# HDN_Control_Data.net
KiCad netlist of a schematic drawn in Altium Designer
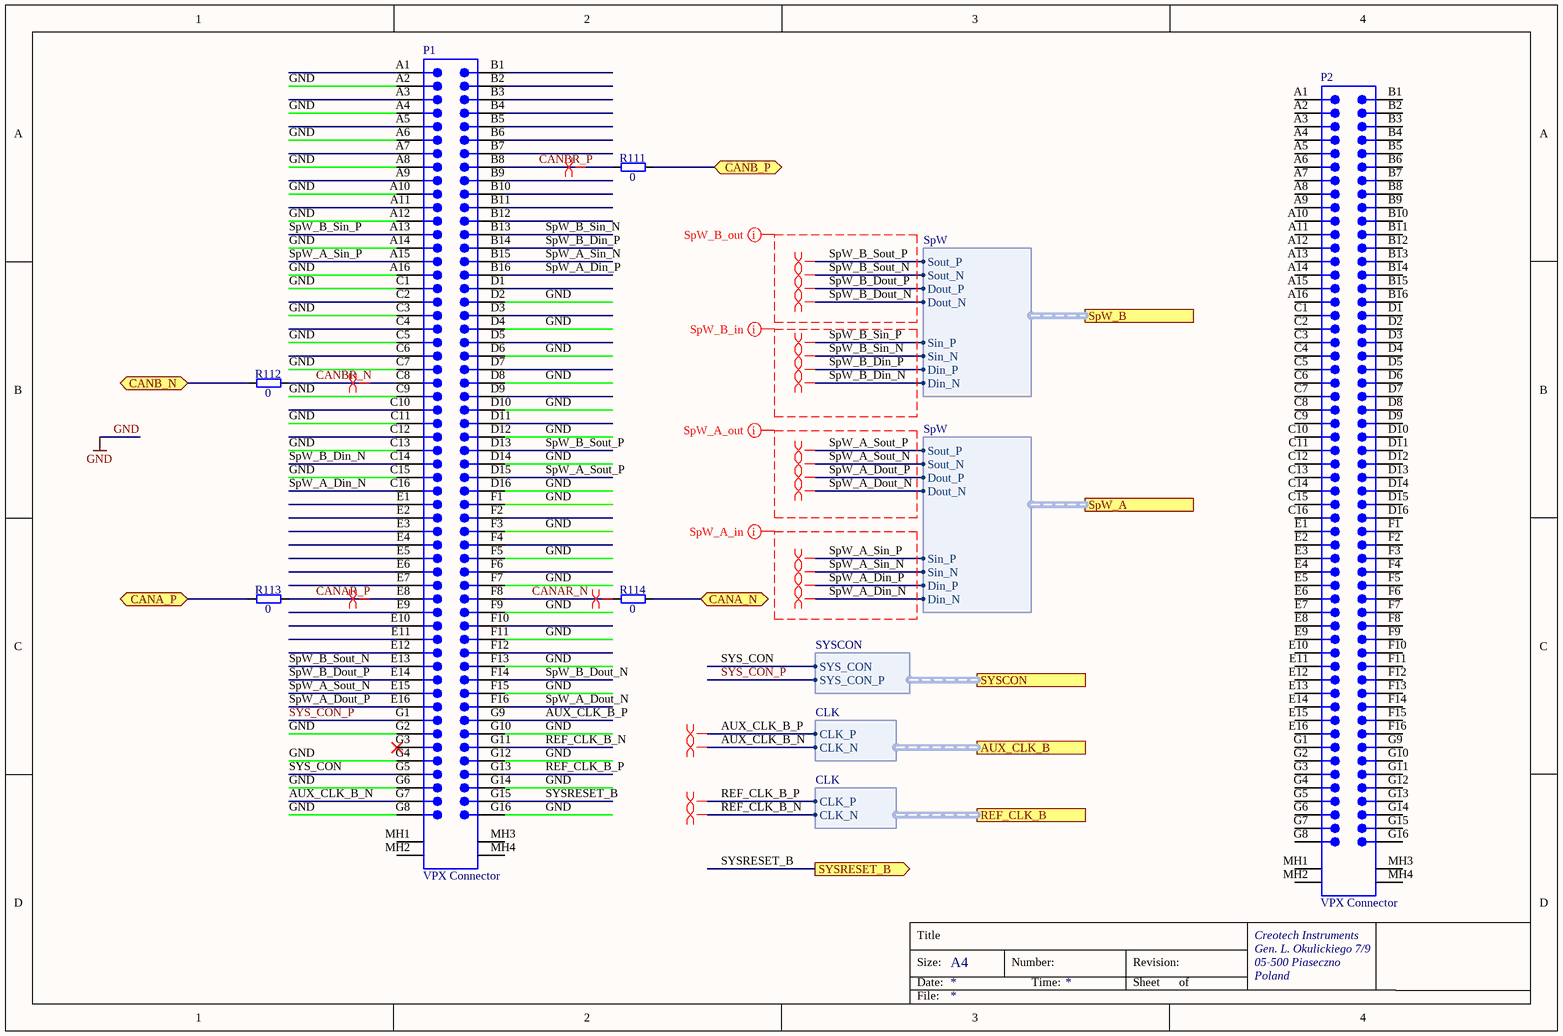
[diagram p0: HDN_Control_Data.SchDoc]

(export (version "E")
  (design (tool "Eeschema 10.0.6"))
  (components
    (comp (ref "P1")
      (value "VPX Connector")
      (footprint "BTB1-8-4H112M")
      (description "Board-to-Board Connector, Right Angle, 7-Row, Pitch 1.8mm, 112-Position")
      (fields (field (name "MANUFACTURER") "TE") (field (name "MANUFACTURER PART NUMBER") "1410187-3"))
      (libsource (lib "LIBRARY_SCH") (part "CON_VPX_1410187-3"))
    )
    (comp (ref "P2")
      (value "VPX Connector")
      (footprint "BTB1-8-4H112M")
      (description "Board-to-Board Connector, Right Angle, 7-Row, Pitch 1.8mm, 112-Position")
      (fields (field (name "MANUFACTURER") "TE") (field (name "MANUFACTURER PART NUMBER") "1410187-3"))
      (libsource (lib "LIBRARY_SCH") (part "CON_VPX_1410187-3"))
    )
    (comp (ref "R111")
      (value "0")
      (footprint "RESC1608X55N")
      (description "Resistor")
      (fields
        (field (name "PART NUMBER") "R0603_0R_JUMPER")
        (field (name "MANUFACTURER") "GENERIC")
        (field (name "AUTHOR") "CERN DEM JLC")
      )
      (libsource (lib "Resistors") (part "Resistor"))
    )
    (comp (ref "R112")
      (value "0")
      (footprint "RESC1608X55N")
      (description "Resistor")
      (fields
        (field (name "PART NUMBER") "R0603_0R_JUMPER")
        (field (name "MANUFACTURER") "GENERIC")
        (field (name "AUTHOR") "CERN DEM JLC")
      )
      (libsource (lib "Resistors") (part "Resistor"))
    )
    (comp (ref "R113")
      (value "0")
      (footprint "RESC1608X55N")
      (description "Resistor")
      (fields
        (field (name "PART NUMBER") "R0603_0R_JUMPER")
        (field (name "MANUFACTURER") "GENERIC")
        (field (name "AUTHOR") "CERN DEM JLC")
      )
      (libsource (lib "Resistors") (part "Resistor"))
    )
    (comp (ref "R114")
      (value "0")
      (footprint "RESC1608X55N")
      (description "Resistor")
      (fields
        (field (name "PART NUMBER") "R0603_0R_JUMPER")
        (field (name "MANUFACTURER") "GENERIC")
        (field (name "AUTHOR") "CERN DEM JLC")
      )
      (libsource (lib "Resistors") (part "Resistor"))
    )
  )
  (nets
    (net (code "4") (name "/AUX_CLK_B_N") (class "Default")
      (node (ref "P1") (pin "G7") (pinfunction "G7_G7") (pintype "passive"))
    )
    (net (code "5") (name "/AUX_CLK_B_P") (class "Default")
      (node (ref "P1") (pin "G9") (pinfunction "G9_G9") (pintype "passive"))
    )
    (net (code "6") (name "/CANAR_N") (class "Default")
      (node (ref "P1") (pin "F8") (pinfunction "F8_F8") (pintype "passive"))
      (node (ref "R114") (pin "1") (pinfunction "1_1") (pintype "passive"))
    )
    (net (code "7") (name "/CANAR_P") (class "Default")
      (node (ref "P1") (pin "E8") (pinfunction "E8_E8") (pintype "passive"))
      (node (ref "R113") (pin "2") (pinfunction "2_2") (pintype "passive"))
    )
    (net (code "8") (name "/CANA_N") (class "Default")
      (node (ref "R114") (pin "2") (pinfunction "2_2") (pintype "passive"))
    )
    (net (code "9") (name "/CANA_P") (class "Default")
      (node (ref "R113") (pin "1") (pinfunction "1_1") (pintype "passive"))
    )
    (net (code "10") (name "/CANBR_N") (class "Default")
      (node (ref "P1") (pin "C8") (pinfunction "C8_C8") (pintype "passive"))
      (node (ref "R112") (pin "2") (pinfunction "2_2") (pintype "passive"))
    )
    (net (code "11") (name "/CANBR_P") (class "Default")
      (node (ref "P1") (pin "B8") (pinfunction "B8_B8") (pintype "passive"))
      (node (ref "R111") (pin "1") (pinfunction "1_1") (pintype "passive"))
    )
    (net (code "12") (name "/CANB_N") (class "Default")
      (node (ref "R112") (pin "1") (pinfunction "1_1") (pintype "passive"))
    )
    (net (code "13") (name "/CANB_P") (class "Default")
      (node (ref "R111") (pin "2") (pinfunction "2_2") (pintype "passive"))
    )
    (net (code "14") (name "/REF_CLK_B_N") (class "Default")
      (node (ref "P1") (pin "G11") (pinfunction "G11_G11") (pintype "passive"))
    )
    (net (code "15") (name "/REF_CLK_B_P") (class "Default")
      (node (ref "P1") (pin "G13") (pinfunction "G13_G13") (pintype "passive"))
    )
    (net (code "16") (name "/SYSRESET_B") (class "Default")
      (node (ref "P1") (pin "G15") (pinfunction "G15_G15") (pintype "passive"))
    )
    (net (code "17") (name "/SYS_CON") (class "Default")
      (node (ref "P1") (pin "G5") (pinfunction "G5_G5") (pintype "passive"))
    )
    (net (code "18") (name "/SYS_CON_P") (class "Default")
      (node (ref "P1") (pin "G1") (pinfunction "G1_G1") (pintype "passive"))
    )
    (net (code "19") (name "/SpW_A_Din_N") (class "Default")
      (node (ref "P1") (pin "C16") (pinfunction "C16_C16") (pintype "passive"))
    )
    (net (code "20") (name "/SpW_A_Din_P") (class "Default")
      (node (ref "P1") (pin "B16") (pinfunction "B16_B16") (pintype "passive"))
    )
    (net (code "21") (name "/SpW_A_Dout_N") (class "Default")
      (node (ref "P1") (pin "F16") (pinfunction "F16_F16") (pintype "passive"))
    )
    (net (code "22") (name "/SpW_A_Dout_P") (class "Default")
      (node (ref "P1") (pin "E16") (pinfunction "E16_E16") (pintype "passive"))
    )
    (net (code "23") (name "/SpW_A_Sin_N") (class "Default")
      (node (ref "P1") (pin "B15") (pinfunction "B15_B15") (pintype "passive"))
    )
    (net (code "24") (name "/SpW_A_Sin_P") (class "Default")
      (node (ref "P1") (pin "A15") (pinfunction "A15_A15") (pintype "passive"))
    )
    (net (code "25") (name "/SpW_A_Sout_N") (class "Default")
      (node (ref "P1") (pin "E15") (pinfunction "E15_E15") (pintype "passive"))
    )
    (net (code "26") (name "/SpW_A_Sout_P") (class "Default")
      (node (ref "P1") (pin "D15") (pinfunction "D15_D15") (pintype "passive"))
    )
    (net (code "27") (name "/SpW_B_Din_N") (class "Default")
      (node (ref "P1") (pin "C14") (pinfunction "C14_C14") (pintype "passive"))
    )
    (net (code "28") (name "/SpW_B_Din_P") (class "Default")
      (node (ref "P1") (pin "B14") (pinfunction "B14_B14") (pintype "passive"))
    )
    (net (code "29") (name "/SpW_B_Dout_N") (class "Default")
      (node (ref "P1") (pin "F14") (pinfunction "F14_F14") (pintype "passive"))
    )
    (net (code "30") (name "/SpW_B_Dout_P") (class "Default")
      (node (ref "P1") (pin "E14") (pinfunction "E14_E14") (pintype "passive"))
    )
    (net (code "31") (name "/SpW_B_Sin_N") (class "Default")
      (node (ref "P1") (pin "B13") (pinfunction "B13_B13") (pintype "passive"))
    )
    (net (code "32") (name "/SpW_B_Sin_P") (class "Default")
      (node (ref "P1") (pin "A13") (pinfunction "A13_A13") (pintype "passive"))
    )
    (net (code "33") (name "/SpW_B_Sout_N") (class "Default")
      (node (ref "P1") (pin "E13") (pinfunction "E13_E13") (pintype "passive"))
    )
    (net (code "34") (name "/SpW_B_Sout_P") (class "Default")
      (node (ref "P1") (pin "D13") (pinfunction "D13_D13") (pintype "passive"))
    )
    (net (code "38") (name "GND") (class "Default")
      (node (ref "P1") (pin "A10") (pinfunction "A10_A10") (pintype "passive"))
      (node (ref "P1") (pin "A12") (pinfunction "A12_A12") (pintype "passive"))
      (node (ref "P1") (pin "A14") (pinfunction "A14_A14") (pintype "passive"))
      (node (ref "P1") (pin "A16") (pinfunction "A16_A16") (pintype "passive"))
      (node (ref "P1") (pin "A2") (pinfunction "A2_A2") (pintype "passive"))
      (node (ref "P1") (pin "A4") (pinfunction "A4_A4") (pintype "passive"))
      (node (ref "P1") (pin "A6") (pinfunction "A6_A6") (pintype "passive"))
      (node (ref "P1") (pin "A8") (pinfunction "A8_A8") (pintype "passive"))
      (node (ref "P1") (pin "C1") (pinfunction "C1_C1") (pintype "passive"))
      (node (ref "P1") (pin "C11") (pinfunction "C11_C11") (pintype "passive"))
      (node (ref "P1") (pin "C13") (pinfunction "C13_C13") (pintype "passive"))
      (node (ref "P1") (pin "C15") (pinfunction "C15_C15") (pintype "passive"))
      (node (ref "P1") (pin "C3") (pinfunction "C3_C3") (pintype "passive"))
      (node (ref "P1") (pin "C5") (pinfunction "C5_C5") (pintype "passive"))
      (node (ref "P1") (pin "C7") (pinfunction "C7_C7") (pintype "passive"))
      (node (ref "P1") (pin "C9") (pinfunction "C9_C9") (pintype "passive"))
      (node (ref "P1") (pin "D10") (pinfunction "D10_D10") (pintype "passive"))
      (node (ref "P1") (pin "D12") (pinfunction "D12_D12") (pintype "passive"))
      (node (ref "P1") (pin "D14") (pinfunction "D14_D14") (pintype "passive"))
      (node (ref "P1") (pin "D16") (pinfunction "D16_D16") (pintype "passive"))
      (node (ref "P1") (pin "D2") (pinfunction "D2_D2") (pintype "passive"))
      (node (ref "P1") (pin "D4") (pinfunction "D4_D4") (pintype "passive"))
      (node (ref "P1") (pin "D6") (pinfunction "D6_D6") (pintype "passive"))
      (node (ref "P1") (pin "D8") (pinfunction "D8_D8") (pintype "passive"))
      (node (ref "P1") (pin "F1") (pinfunction "F1_F1") (pintype "passive"))
      (node (ref "P1") (pin "F11") (pinfunction "F11_F11") (pintype "passive"))
      (node (ref "P1") (pin "F13") (pinfunction "F13_F13") (pintype "passive"))
      (node (ref "P1") (pin "F15") (pinfunction "F15_F15") (pintype "passive"))
      (node (ref "P1") (pin "F3") (pinfunction "F3_F3") (pintype "passive"))
      (node (ref "P1") (pin "F5") (pinfunction "F5_F5") (pintype "passive"))
      (node (ref "P1") (pin "F7") (pinfunction "F7_F7") (pintype "passive"))
      (node (ref "P1") (pin "F9") (pinfunction "F9_F9") (pintype "passive"))
      (node (ref "P1") (pin "G10") (pinfunction "G10_G10") (pintype "passive"))
      (node (ref "P1") (pin "G12") (pinfunction "G12_G12") (pintype "passive"))
      (node (ref "P1") (pin "G14") (pinfunction "G14_G14") (pintype "passive"))
      (node (ref "P1") (pin "G16") (pinfunction "G16_G16") (pintype "passive"))
      (node (ref "P1") (pin "G2") (pinfunction "G2_G2") (pintype "passive"))
      (node (ref "P1") (pin "G4") (pinfunction "G4_G4") (pintype "passive"))
      (node (ref "P1") (pin "G6") (pinfunction "G6_G6") (pintype "passive"))
      (node (ref "P1") (pin "G8") (pinfunction "G8_G8") (pintype "passive"))
    )
    (net (code "39") (name "unconnected-(P1-PadA1)") (class "Default")
      (node (ref "P1") (pin "A1") (pinfunction "A1_A1") (pintype "passive"))
    )
    (net (code "40") (name "unconnected-(P1-PadA3)") (class "Default")
      (node (ref "P1") (pin "A3") (pinfunction "A3_A3") (pintype "passive"))
    )
    (net (code "41") (name "unconnected-(P1-PadA5)") (class "Default")
      (node (ref "P1") (pin "A5") (pinfunction "A5_A5") (pintype "passive"))
    )
    (net (code "42") (name "unconnected-(P1-PadA7)") (class "Default")
      (node (ref "P1") (pin "A7") (pinfunction "A7_A7") (pintype "passive"))
    )
    (net (code "43") (name "unconnected-(P1-PadA9)") (class "Default")
      (node (ref "P1") (pin "A9") (pinfunction "A9_A9") (pintype "passive"))
    )
    (net (code "44") (name "unconnected-(P1-PadA11)") (class "Default")
      (node (ref "P1") (pin "A11") (pinfunction "A11_A11") (pintype "passive"))
    )
    (net (code "45") (name "unconnected-(P1-PadB1)") (class "Default")
      (node (ref "P1") (pin "B1") (pinfunction "B1_B1") (pintype "passive"))
    )
    (net (code "46") (name "unconnected-(P1-PadB2)") (class "Default")
      (node (ref "P1") (pin "B2") (pinfunction "B2_B2") (pintype "passive"))
    )
    (net (code "47") (name "unconnected-(P1-PadB3)") (class "Default")
      (node (ref "P1") (pin "B3") (pinfunction "B3_B3") (pintype "passive"))
    )
    (net (code "48") (name "unconnected-(P1-PadB4)") (class "Default")
      (node (ref "P1") (pin "B4") (pinfunction "B4_B4") (pintype "passive"))
    )
    (net (code "49") (name "unconnected-(P1-PadB5)") (class "Default")
      (node (ref "P1") (pin "B5") (pinfunction "B5_B5") (pintype "passive"))
    )
    (net (code "50") (name "unconnected-(P1-PadB6)") (class "Default")
      (node (ref "P1") (pin "B6") (pinfunction "B6_B6") (pintype "passive"))
    )
    (net (code "51") (name "unconnected-(P1-PadB7)") (class "Default")
      (node (ref "P1") (pin "B7") (pinfunction "B7_B7") (pintype "passive"))
    )
    (net (code "52") (name "unconnected-(P1-PadB9)") (class "Default")
      (node (ref "P1") (pin "B9") (pinfunction "B9_B9") (pintype "passive"))
    )
    (net (code "53") (name "unconnected-(P1-PadB10)") (class "Default")
      (node (ref "P1") (pin "B10") (pinfunction "B10_B10") (pintype "passive"))
    )
    (net (code "54") (name "unconnected-(P1-PadB11)") (class "Default")
      (node (ref "P1") (pin "B11") (pinfunction "B11_B11") (pintype "passive"))
    )
    (net (code "55") (name "unconnected-(P1-PadB12)") (class "Default")
      (node (ref "P1") (pin "B12") (pinfunction "B12_B12") (pintype "passive"))
    )
    (net (code "56") (name "unconnected-(P1-PadC2)") (class "Default")
      (node (ref "P1") (pin "C2") (pinfunction "C2_C2") (pintype "passive"))
    )
    (net (code "57") (name "unconnected-(P1-PadC4)") (class "Default")
      (node (ref "P1") (pin "C4") (pinfunction "C4_C4") (pintype "passive"))
    )
    (net (code "58") (name "unconnected-(P1-PadC6)") (class "Default")
      (node (ref "P1") (pin "C6") (pinfunction "C6_C6") (pintype "passive"))
    )
    (net (code "59") (name "unconnected-(P1-PadC10)") (class "Default")
      (node (ref "P1") (pin "C10") (pinfunction "C10_C10") (pintype "passive"))
    )
    (net (code "60") (name "unconnected-(P1-PadC12)") (class "Default")
      (node (ref "P1") (pin "C12") (pinfunction "C12_C12") (pintype "passive"))
    )
    (net (code "61") (name "unconnected-(P1-PadD1)") (class "Default")
      (node (ref "P1") (pin "D1") (pinfunction "D1_D1") (pintype "passive"))
    )
    (net (code "62") (name "unconnected-(P1-PadD3)") (class "Default")
      (node (ref "P1") (pin "D3") (pinfunction "D3_D3") (pintype "passive"))
    )
    (net (code "63") (name "unconnected-(P1-PadD5)") (class "Default")
      (node (ref "P1") (pin "D5") (pinfunction "D5_D5") (pintype "passive"))
    )
    (net (code "64") (name "unconnected-(P1-PadD7)") (class "Default")
      (node (ref "P1") (pin "D7") (pinfunction "D7_D7") (pintype "passive"))
    )
    (net (code "65") (name "unconnected-(P1-PadD9)") (class "Default")
      (node (ref "P1") (pin "D9") (pinfunction "D9_D9") (pintype "passive"))
    )
    (net (code "66") (name "unconnected-(P1-PadD11)") (class "Default")
      (node (ref "P1") (pin "D11") (pinfunction "D11_D11") (pintype "passive"))
    )
    (net (code "67") (name "unconnected-(P1-PadE1)") (class "Default")
      (node (ref "P1") (pin "E1") (pinfunction "E1_E1") (pintype "passive"))
    )
    (net (code "68") (name "unconnected-(P1-PadE2)") (class "Default")
      (node (ref "P1") (pin "E2") (pinfunction "E2_E2") (pintype "passive"))
    )
    (net (code "69") (name "unconnected-(P1-PadE3)") (class "Default")
      (node (ref "P1") (pin "E3") (pinfunction "E3_E3") (pintype "passive"))
    )
    (net (code "70") (name "unconnected-(P1-PadE4)") (class "Default")
      (node (ref "P1") (pin "E4") (pinfunction "E4_E4") (pintype "passive"))
    )
    (net (code "71") (name "unconnected-(P1-PadE5)") (class "Default")
      (node (ref "P1") (pin "E5") (pinfunction "E5_E5") (pintype "passive"))
    )
    (net (code "72") (name "unconnected-(P1-PadE6)") (class "Default")
      (node (ref "P1") (pin "E6") (pinfunction "E6_E6") (pintype "passive"))
    )
    (net (code "73") (name "unconnected-(P1-PadE7)") (class "Default")
      (node (ref "P1") (pin "E7") (pinfunction "E7_E7") (pintype "passive"))
    )
    (net (code "74") (name "unconnected-(P1-PadE9)") (class "Default")
      (node (ref "P1") (pin "E9") (pinfunction "E9_E9") (pintype "passive"))
    )
    (net (code "75") (name "unconnected-(P1-PadE10)") (class "Default")
      (node (ref "P1") (pin "E10") (pinfunction "E10_E10") (pintype "passive"))
    )
    (net (code "76") (name "unconnected-(P1-PadE11)") (class "Default")
      (node (ref "P1") (pin "E11") (pinfunction "E11_E11") (pintype "passive"))
    )
    (net (code "77") (name "unconnected-(P1-PadE12)") (class "Default")
      (node (ref "P1") (pin "E12") (pinfunction "E12_E12") (pintype "passive"))
    )
    (net (code "78") (name "unconnected-(P1-PadF2)") (class "Default")
      (node (ref "P1") (pin "F2") (pinfunction "F2_F2") (pintype "passive"))
    )
    (net (code "79") (name "unconnected-(P1-PadF4)") (class "Default")
      (node (ref "P1") (pin "F4") (pinfunction "F4_F4") (pintype "passive"))
    )
    (net (code "80") (name "unconnected-(P1-PadF6)") (class "Default")
      (node (ref "P1") (pin "F6") (pinfunction "F6_F6") (pintype "passive"))
    )
    (net (code "81") (name "unconnected-(P1-PadF10)") (class "Default")
      (node (ref "P1") (pin "F10") (pinfunction "F10_F10") (pintype "passive"))
    )
    (net (code "82") (name "unconnected-(P1-PadF12)") (class "Default")
      (node (ref "P1") (pin "F12") (pinfunction "F12_F12") (pintype "passive"))
    )
    (net (code "83") (name "unconnected-(P1-PadG3)") (class "Default")
      (node (ref "P1") (pin "G3") (pinfunction "G3_G3") (pintype "passive+no_connect"))
    )
    (net (code "84") (name "unconnected-(P1-PadMH1)") (class "Default")
      (node (ref "P1") (pin "MH1") (pinfunction "MH1_MH1") (pintype "passive"))
    )
    (net (code "85") (name "unconnected-(P1-PadMH2)") (class "Default")
      (node (ref "P1") (pin "MH2") (pinfunction "MH2_MH2") (pintype "passive"))
    )
    (net (code "86") (name "unconnected-(P1-PadMH3)") (class "Default")
      (node (ref "P1") (pin "MH3") (pinfunction "MH3_MH3") (pintype "passive"))
    )
    (net (code "87") (name "unconnected-(P1-PadMH4)") (class "Default")
      (node (ref "P1") (pin "MH4") (pinfunction "MH4_MH4") (pintype "passive"))
    )
    (net (code "88") (name "unconnected-(P2-PadA1)") (class "Default")
      (node (ref "P2") (pin "A1") (pinfunction "A1_A1") (pintype "passive"))
    )
    (net (code "89") (name "unconnected-(P2-PadA2)") (class "Default")
      (node (ref "P2") (pin "A2") (pinfunction "A2_A2") (pintype "passive"))
    )
    (net (code "90") (name "unconnected-(P2-PadA3)") (class "Default")
      (node (ref "P2") (pin "A3") (pinfunction "A3_A3") (pintype "passive"))
    )
    (net (code "91") (name "unconnected-(P2-PadA4)") (class "Default")
      (node (ref "P2") (pin "A4") (pinfunction "A4_A4") (pintype "passive"))
    )
    (net (code "92") (name "unconnected-(P2-PadA5)") (class "Default")
      (node (ref "P2") (pin "A5") (pinfunction "A5_A5") (pintype "passive"))
    )
    (net (code "93") (name "unconnected-(P2-PadA6)") (class "Default")
      (node (ref "P2") (pin "A6") (pinfunction "A6_A6") (pintype "passive"))
    )
    (net (code "94") (name "unconnected-(P2-PadA7)") (class "Default")
      (node (ref "P2") (pin "A7") (pinfunction "A7_A7") (pintype "passive"))
    )
    (net (code "95") (name "unconnected-(P2-PadA8)") (class "Default")
      (node (ref "P2") (pin "A8") (pinfunction "A8_A8") (pintype "passive"))
    )
    (net (code "96") (name "unconnected-(P2-PadA9)") (class "Default")
      (node (ref "P2") (pin "A9") (pinfunction "A9_A9") (pintype "passive"))
    )
    (net (code "97") (name "unconnected-(P2-PadA10)") (class "Default")
      (node (ref "P2") (pin "A10") (pinfunction "A10_A10") (pintype "passive"))
    )
    (net (code "98") (name "unconnected-(P2-PadA11)") (class "Default")
      (node (ref "P2") (pin "A11") (pinfunction "A11_A11") (pintype "passive"))
    )
    (net (code "99") (name "unconnected-(P2-PadA12)") (class "Default")
      (node (ref "P2") (pin "A12") (pinfunction "A12_A12") (pintype "passive"))
    )
    (net (code "100") (name "unconnected-(P2-PadA13)") (class "Default")
      (node (ref "P2") (pin "A13") (pinfunction "A13_A13") (pintype "passive"))
    )
    (net (code "101") (name "unconnected-(P2-PadA14)") (class "Default")
      (node (ref "P2") (pin "A14") (pinfunction "A14_A14") (pintype "passive"))
    )
    (net (code "102") (name "unconnected-(P2-PadA15)") (class "Default")
      (node (ref "P2") (pin "A15") (pinfunction "A15_A15") (pintype "passive"))
    )
    (net (code "103") (name "unconnected-(P2-PadA16)") (class "Default")
      (node (ref "P2") (pin "A16") (pinfunction "A16_A16") (pintype "passive"))
    )
    (net (code "104") (name "unconnected-(P2-PadB1)") (class "Default")
      (node (ref "P2") (pin "B1") (pinfunction "B1_B1") (pintype "passive"))
    )
    (net (code "105") (name "unconnected-(P2-PadB2)") (class "Default")
      (node (ref "P2") (pin "B2") (pinfunction "B2_B2") (pintype "passive"))
    )
    (net (code "106") (name "unconnected-(P2-PadB3)") (class "Default")
      (node (ref "P2") (pin "B3") (pinfunction "B3_B3") (pintype "passive"))
    )
    (net (code "107") (name "unconnected-(P2-PadB4)") (class "Default")
      (node (ref "P2") (pin "B4") (pinfunction "B4_B4") (pintype "passive"))
    )
    (net (code "108") (name "unconnected-(P2-PadB5)") (class "Default")
      (node (ref "P2") (pin "B5") (pinfunction "B5_B5") (pintype "passive"))
    )
    (net (code "109") (name "unconnected-(P2-PadB6)") (class "Default")
      (node (ref "P2") (pin "B6") (pinfunction "B6_B6") (pintype "passive"))
    )
    (net (code "110") (name "unconnected-(P2-PadB7)") (class "Default")
      (node (ref "P2") (pin "B7") (pinfunction "B7_B7") (pintype "passive"))
    )
    (net (code "111") (name "unconnected-(P2-PadB8)") (class "Default")
      (node (ref "P2") (pin "B8") (pinfunction "B8_B8") (pintype "passive"))
    )
    (net (code "112") (name "unconnected-(P2-PadB9)") (class "Default")
      (node (ref "P2") (pin "B9") (pinfunction "B9_B9") (pintype "passive"))
    )
    (net (code "113") (name "unconnected-(P2-PadB10)") (class "Default")
      (node (ref "P2") (pin "B10") (pinfunction "B10_B10") (pintype "passive"))
    )
    (net (code "114") (name "unconnected-(P2-PadB11)") (class "Default")
      (node (ref "P2") (pin "B11") (pinfunction "B11_B11") (pintype "passive"))
    )
    (net (code "115") (name "unconnected-(P2-PadB12)") (class "Default")
      (node (ref "P2") (pin "B12") (pinfunction "B12_B12") (pintype "passive"))
    )
    (net (code "116") (name "unconnected-(P2-PadB13)") (class "Default")
      (node (ref "P2") (pin "B13") (pinfunction "B13_B13") (pintype "passive"))
    )
    (net (code "117") (name "unconnected-(P2-PadB14)") (class "Default")
      (node (ref "P2") (pin "B14") (pinfunction "B14_B14") (pintype "passive"))
    )
    (net (code "118") (name "unconnected-(P2-PadB15)") (class "Default")
      (node (ref "P2") (pin "B15") (pinfunction "B15_B15") (pintype "passive"))
    )
    (net (code "119") (name "unconnected-(P2-PadB16)") (class "Default")
      (node (ref "P2") (pin "B16") (pinfunction "B16_B16") (pintype "passive"))
    )
    (net (code "120") (name "unconnected-(P2-PadC1)") (class "Default")
      (node (ref "P2") (pin "C1") (pinfunction "C1_C1") (pintype "passive"))
    )
    (net (code "121") (name "unconnected-(P2-PadC2)") (class "Default")
      (node (ref "P2") (pin "C2") (pinfunction "C2_C2") (pintype "passive"))
    )
    (net (code "122") (name "unconnected-(P2-PadC3)") (class "Default")
      (node (ref "P2") (pin "C3") (pinfunction "C3_C3") (pintype "passive"))
    )
    (net (code "123") (name "unconnected-(P2-PadC4)") (class "Default")
      (node (ref "P2") (pin "C4") (pinfunction "C4_C4") (pintype "passive"))
    )
    (net (code "124") (name "unconnected-(P2-PadC5)") (class "Default")
      (node (ref "P2") (pin "C5") (pinfunction "C5_C5") (pintype "passive"))
    )
    (net (code "125") (name "unconnected-(P2-PadC6)") (class "Default")
      (node (ref "P2") (pin "C6") (pinfunction "C6_C6") (pintype "passive"))
    )
    (net (code "126") (name "unconnected-(P2-PadC7)") (class "Default")
      (node (ref "P2") (pin "C7") (pinfunction "C7_C7") (pintype "passive"))
    )
    (net (code "127") (name "unconnected-(P2-PadC8)") (class "Default")
      (node (ref "P2") (pin "C8") (pinfunction "C8_C8") (pintype "passive"))
    )
    (net (code "128") (name "unconnected-(P2-PadC9)") (class "Default")
      (node (ref "P2") (pin "C9") (pinfunction "C9_C9") (pintype "passive"))
    )
    (net (code "129") (name "unconnected-(P2-PadC10)") (class "Default")
      (node (ref "P2") (pin "C10") (pinfunction "C10_C10") (pintype "passive"))
    )
    (net (code "130") (name "unconnected-(P2-PadC11)") (class "Default")
      (node (ref "P2") (pin "C11") (pinfunction "C11_C11") (pintype "passive"))
    )
    (net (code "131") (name "unconnected-(P2-PadC12)") (class "Default")
      (node (ref "P2") (pin "C12") (pinfunction "C12_C12") (pintype "passive"))
    )
    (net (code "132") (name "unconnected-(P2-PadC13)") (class "Default")
      (node (ref "P2") (pin "C13") (pinfunction "C13_C13") (pintype "passive"))
    )
    (net (code "133") (name "unconnected-(P2-PadC14)") (class "Default")
      (node (ref "P2") (pin "C14") (pinfunction "C14_C14") (pintype "passive"))
    )
    (net (code "134") (name "unconnected-(P2-PadC15)") (class "Default")
      (node (ref "P2") (pin "C15") (pinfunction "C15_C15") (pintype "passive"))
    )
    (net (code "135") (name "unconnected-(P2-PadC16)") (class "Default")
      (node (ref "P2") (pin "C16") (pinfunction "C16_C16") (pintype "passive"))
    )
    (net (code "136") (name "unconnected-(P2-PadD1)") (class "Default")
      (node (ref "P2") (pin "D1") (pinfunction "D1_D1") (pintype "passive"))
    )
    (net (code "137") (name "unconnected-(P2-PadD2)") (class "Default")
      (node (ref "P2") (pin "D2") (pinfunction "D2_D2") (pintype "passive"))
    )
    (net (code "138") (name "unconnected-(P2-PadD3)") (class "Default")
      (node (ref "P2") (pin "D3") (pinfunction "D3_D3") (pintype "passive"))
    )
    (net (code "139") (name "unconnected-(P2-PadD4)") (class "Default")
      (node (ref "P2") (pin "D4") (pinfunction "D4_D4") (pintype "passive"))
    )
    (net (code "140") (name "unconnected-(P2-PadD5)") (class "Default")
      (node (ref "P2") (pin "D5") (pinfunction "D5_D5") (pintype "passive"))
    )
    (net (code "141") (name "unconnected-(P2-PadD6)") (class "Default")
      (node (ref "P2") (pin "D6") (pinfunction "D6_D6") (pintype "passive"))
    )
    (net (code "142") (name "unconnected-(P2-PadD7)") (class "Default")
      (node (ref "P2") (pin "D7") (pinfunction "D7_D7") (pintype "passive"))
    )
    (net (code "143") (name "unconnected-(P2-PadD8)") (class "Default")
      (node (ref "P2") (pin "D8") (pinfunction "D8_D8") (pintype "passive"))
    )
    (net (code "144") (name "unconnected-(P2-PadD9)") (class "Default")
      (node (ref "P2") (pin "D9") (pinfunction "D9_D9") (pintype "passive"))
    )
    (net (code "145") (name "unconnected-(P2-PadD10)") (class "Default")
      (node (ref "P2") (pin "D10") (pinfunction "D10_D10") (pintype "passive"))
    )
    (net (code "146") (name "unconnected-(P2-PadD11)") (class "Default")
      (node (ref "P2") (pin "D11") (pinfunction "D11_D11") (pintype "passive"))
    )
    (net (code "147") (name "unconnected-(P2-PadD12)") (class "Default")
      (node (ref "P2") (pin "D12") (pinfunction "D12_D12") (pintype "passive"))
    )
    (net (code "148") (name "unconnected-(P2-PadD13)") (class "Default")
      (node (ref "P2") (pin "D13") (pinfunction "D13_D13") (pintype "passive"))
    )
    (net (code "149") (name "unconnected-(P2-PadD14)") (class "Default")
      (node (ref "P2") (pin "D14") (pinfunction "D14_D14") (pintype "passive"))
    )
    (net (code "150") (name "unconnected-(P2-PadD15)") (class "Default")
      (node (ref "P2") (pin "D15") (pinfunction "D15_D15") (pintype "passive"))
    )
    (net (code "151") (name "unconnected-(P2-PadD16)") (class "Default")
      (node (ref "P2") (pin "D16") (pinfunction "D16_D16") (pintype "passive"))
    )
    (net (code "152") (name "unconnected-(P2-PadE1)") (class "Default")
      (node (ref "P2") (pin "E1") (pinfunction "E1_E1") (pintype "passive"))
    )
    (net (code "153") (name "unconnected-(P2-PadE2)") (class "Default")
      (node (ref "P2") (pin "E2") (pinfunction "E2_E2") (pintype "passive"))
    )
    (net (code "154") (name "unconnected-(P2-PadE3)") (class "Default")
      (node (ref "P2") (pin "E3") (pinfunction "E3_E3") (pintype "passive"))
    )
    (net (code "155") (name "unconnected-(P2-PadE4)") (class "Default")
      (node (ref "P2") (pin "E4") (pinfunction "E4_E4") (pintype "passive"))
    )
    (net (code "156") (name "unconnected-(P2-PadE5)") (class "Default")
      (node (ref "P2") (pin "E5") (pinfunction "E5_E5") (pintype "passive"))
    )
    (net (code "157") (name "unconnected-(P2-PadE6)") (class "Default")
      (node (ref "P2") (pin "E6") (pinfunction "E6_E6") (pintype "passive"))
    )
    (net (code "158") (name "unconnected-(P2-PadE7)") (class "Default")
      (node (ref "P2") (pin "E7") (pinfunction "E7_E7") (pintype "passive"))
    )
    (net (code "159") (name "unconnected-(P2-PadE8)") (class "Default")
      (node (ref "P2") (pin "E8") (pinfunction "E8_E8") (pintype "passive"))
    )
    (net (code "160") (name "unconnected-(P2-PadE9)") (class "Default")
      (node (ref "P2") (pin "E9") (pinfunction "E9_E9") (pintype "passive"))
    )
    (net (code "161") (name "unconnected-(P2-PadE10)") (class "Default")
      (node (ref "P2") (pin "E10") (pinfunction "E10_E10") (pintype "passive"))
    )
    (net (code "162") (name "unconnected-(P2-PadE11)") (class "Default")
      (node (ref "P2") (pin "E11") (pinfunction "E11_E11") (pintype "passive"))
    )
    (net (code "163") (name "unconnected-(P2-PadE12)") (class "Default")
      (node (ref "P2") (pin "E12") (pinfunction "E12_E12") (pintype "passive"))
    )
    (net (code "164") (name "unconnected-(P2-PadE13)") (class "Default")
      (node (ref "P2") (pin "E13") (pinfunction "E13_E13") (pintype "passive"))
    )
    (net (code "165") (name "unconnected-(P2-PadE14)") (class "Default")
      (node (ref "P2") (pin "E14") (pinfunction "E14_E14") (pintype "passive"))
    )
    (net (code "166") (name "unconnected-(P2-PadE15)") (class "Default")
      (node (ref "P2") (pin "E15") (pinfunction "E15_E15") (pintype "passive"))
    )
    (net (code "167") (name "unconnected-(P2-PadE16)") (class "Default")
      (node (ref "P2") (pin "E16") (pinfunction "E16_E16") (pintype "passive"))
    )
    (net (code "168") (name "unconnected-(P2-PadF1)") (class "Default")
      (node (ref "P2") (pin "F1") (pinfunction "F1_F1") (pintype "passive"))
    )
    (net (code "169") (name "unconnected-(P2-PadF2)") (class "Default")
      (node (ref "P2") (pin "F2") (pinfunction "F2_F2") (pintype "passive"))
    )
    (net (code "170") (name "unconnected-(P2-PadF3)") (class "Default")
      (node (ref "P2") (pin "F3") (pinfunction "F3_F3") (pintype "passive"))
    )
    (net (code "171") (name "unconnected-(P2-PadF4)") (class "Default")
      (node (ref "P2") (pin "F4") (pinfunction "F4_F4") (pintype "passive"))
    )
    (net (code "172") (name "unconnected-(P2-PadF5)") (class "Default")
      (node (ref "P2") (pin "F5") (pinfunction "F5_F5") (pintype "passive"))
    )
    (net (code "173") (name "unconnected-(P2-PadF6)") (class "Default")
      (node (ref "P2") (pin "F6") (pinfunction "F6_F6") (pintype "passive"))
    )
    (net (code "174") (name "unconnected-(P2-PadF7)") (class "Default")
      (node (ref "P2") (pin "F7") (pinfunction "F7_F7") (pintype "passive"))
    )
    (net (code "175") (name "unconnected-(P2-PadF8)") (class "Default")
      (node (ref "P2") (pin "F8") (pinfunction "F8_F8") (pintype "passive"))
    )
    (net (code "176") (name "unconnected-(P2-PadF9)") (class "Default")
      (node (ref "P2") (pin "F9") (pinfunction "F9_F9") (pintype "passive"))
    )
    (net (code "177") (name "unconnected-(P2-PadF10)") (class "Default")
      (node (ref "P2") (pin "F10") (pinfunction "F10_F10") (pintype "passive"))
    )
    (net (code "178") (name "unconnected-(P2-PadF11)") (class "Default")
      (node (ref "P2") (pin "F11") (pinfunction "F11_F11") (pintype "passive"))
    )
    (net (code "179") (name "unconnected-(P2-PadF12)") (class "Default")
      (node (ref "P2") (pin "F12") (pinfunction "F12_F12") (pintype "passive"))
    )
    (net (code "180") (name "unconnected-(P2-PadF13)") (class "Default")
      (node (ref "P2") (pin "F13") (pinfunction "F13_F13") (pintype "passive"))
    )
    (net (code "181") (name "unconnected-(P2-PadF14)") (class "Default")
      (node (ref "P2") (pin "F14") (pinfunction "F14_F14") (pintype "passive"))
    )
    (net (code "182") (name "unconnected-(P2-PadF15)") (class "Default")
      (node (ref "P2") (pin "F15") (pinfunction "F15_F15") (pintype "passive"))
    )
    (net (code "183") (name "unconnected-(P2-PadF16)") (class "Default")
      (node (ref "P2") (pin "F16") (pinfunction "F16_F16") (pintype "passive"))
    )
    (net (code "184") (name "unconnected-(P2-PadG1)") (class "Default")
      (node (ref "P2") (pin "G1") (pinfunction "G1_G1") (pintype "passive"))
    )
    (net (code "185") (name "unconnected-(P2-PadG2)") (class "Default")
      (node (ref "P2") (pin "G2") (pinfunction "G2_G2") (pintype "passive"))
    )
    (net (code "186") (name "unconnected-(P2-PadG3)") (class "Default")
      (node (ref "P2") (pin "G3") (pinfunction "G3_G3") (pintype "passive"))
    )
    (net (code "187") (name "unconnected-(P2-PadG4)") (class "Default")
      (node (ref "P2") (pin "G4") (pinfunction "G4_G4") (pintype "passive"))
    )
    (net (code "188") (name "unconnected-(P2-PadG5)") (class "Default")
      (node (ref "P2") (pin "G5") (pinfunction "G5_G5") (pintype "passive"))
    )
    (net (code "189") (name "unconnected-(P2-PadG6)") (class "Default")
      (node (ref "P2") (pin "G6") (pinfunction "G6_G6") (pintype "passive"))
    )
    (net (code "190") (name "unconnected-(P2-PadG7)") (class "Default")
      (node (ref "P2") (pin "G7") (pinfunction "G7_G7") (pintype "passive"))
    )
    (net (code "191") (name "unconnected-(P2-PadG8)") (class "Default")
      (node (ref "P2") (pin "G8") (pinfunction "G8_G8") (pintype "passive"))
    )
    (net (code "192") (name "unconnected-(P2-PadG9)") (class "Default")
      (node (ref "P2") (pin "G9") (pinfunction "G9_G9") (pintype "passive"))
    )
    (net (code "193") (name "unconnected-(P2-PadG10)") (class "Default")
      (node (ref "P2") (pin "G10") (pinfunction "G10_G10") (pintype "passive"))
    )
    (net (code "194") (name "unconnected-(P2-PadG11)") (class "Default")
      (node (ref "P2") (pin "G11") (pinfunction "G11_G11") (pintype "passive"))
    )
    (net (code "195") (name "unconnected-(P2-PadG12)") (class "Default")
      (node (ref "P2") (pin "G12") (pinfunction "G12_G12") (pintype "passive"))
    )
    (net (code "196") (name "unconnected-(P2-PadG13)") (class "Default")
      (node (ref "P2") (pin "G13") (pinfunction "G13_G13") (pintype "passive"))
    )
    (net (code "197") (name "unconnected-(P2-PadG14)") (class "Default")
      (node (ref "P2") (pin "G14") (pinfunction "G14_G14") (pintype "passive"))
    )
    (net (code "198") (name "unconnected-(P2-PadG15)") (class "Default")
      (node (ref "P2") (pin "G15") (pinfunction "G15_G15") (pintype "passive"))
    )
    (net (code "199") (name "unconnected-(P2-PadG16)") (class "Default")
      (node (ref "P2") (pin "G16") (pinfunction "G16_G16") (pintype "passive"))
    )
    (net (code "200") (name "unconnected-(P2-PadMH1)") (class "Default")
      (node (ref "P2") (pin "MH1") (pinfunction "MH1_MH1") (pintype "passive"))
    )
    (net (code "201") (name "unconnected-(P2-PadMH2)") (class "Default")
      (node (ref "P2") (pin "MH2") (pinfunction "MH2_MH2") (pintype "passive"))
    )
    (net (code "202") (name "unconnected-(P2-PadMH3)") (class "Default")
      (node (ref "P2") (pin "MH3") (pinfunction "MH3_MH3") (pintype "passive"))
    )
    (net (code "203") (name "unconnected-(P2-PadMH4)") (class "Default")
      (node (ref "P2") (pin "MH4") (pinfunction "MH4_MH4") (pintype "passive"))
    )
  )
)
